# Filters_3Stage_Circuit_Manual.net
KiCad netlist of a schematic drawn in EAGLE
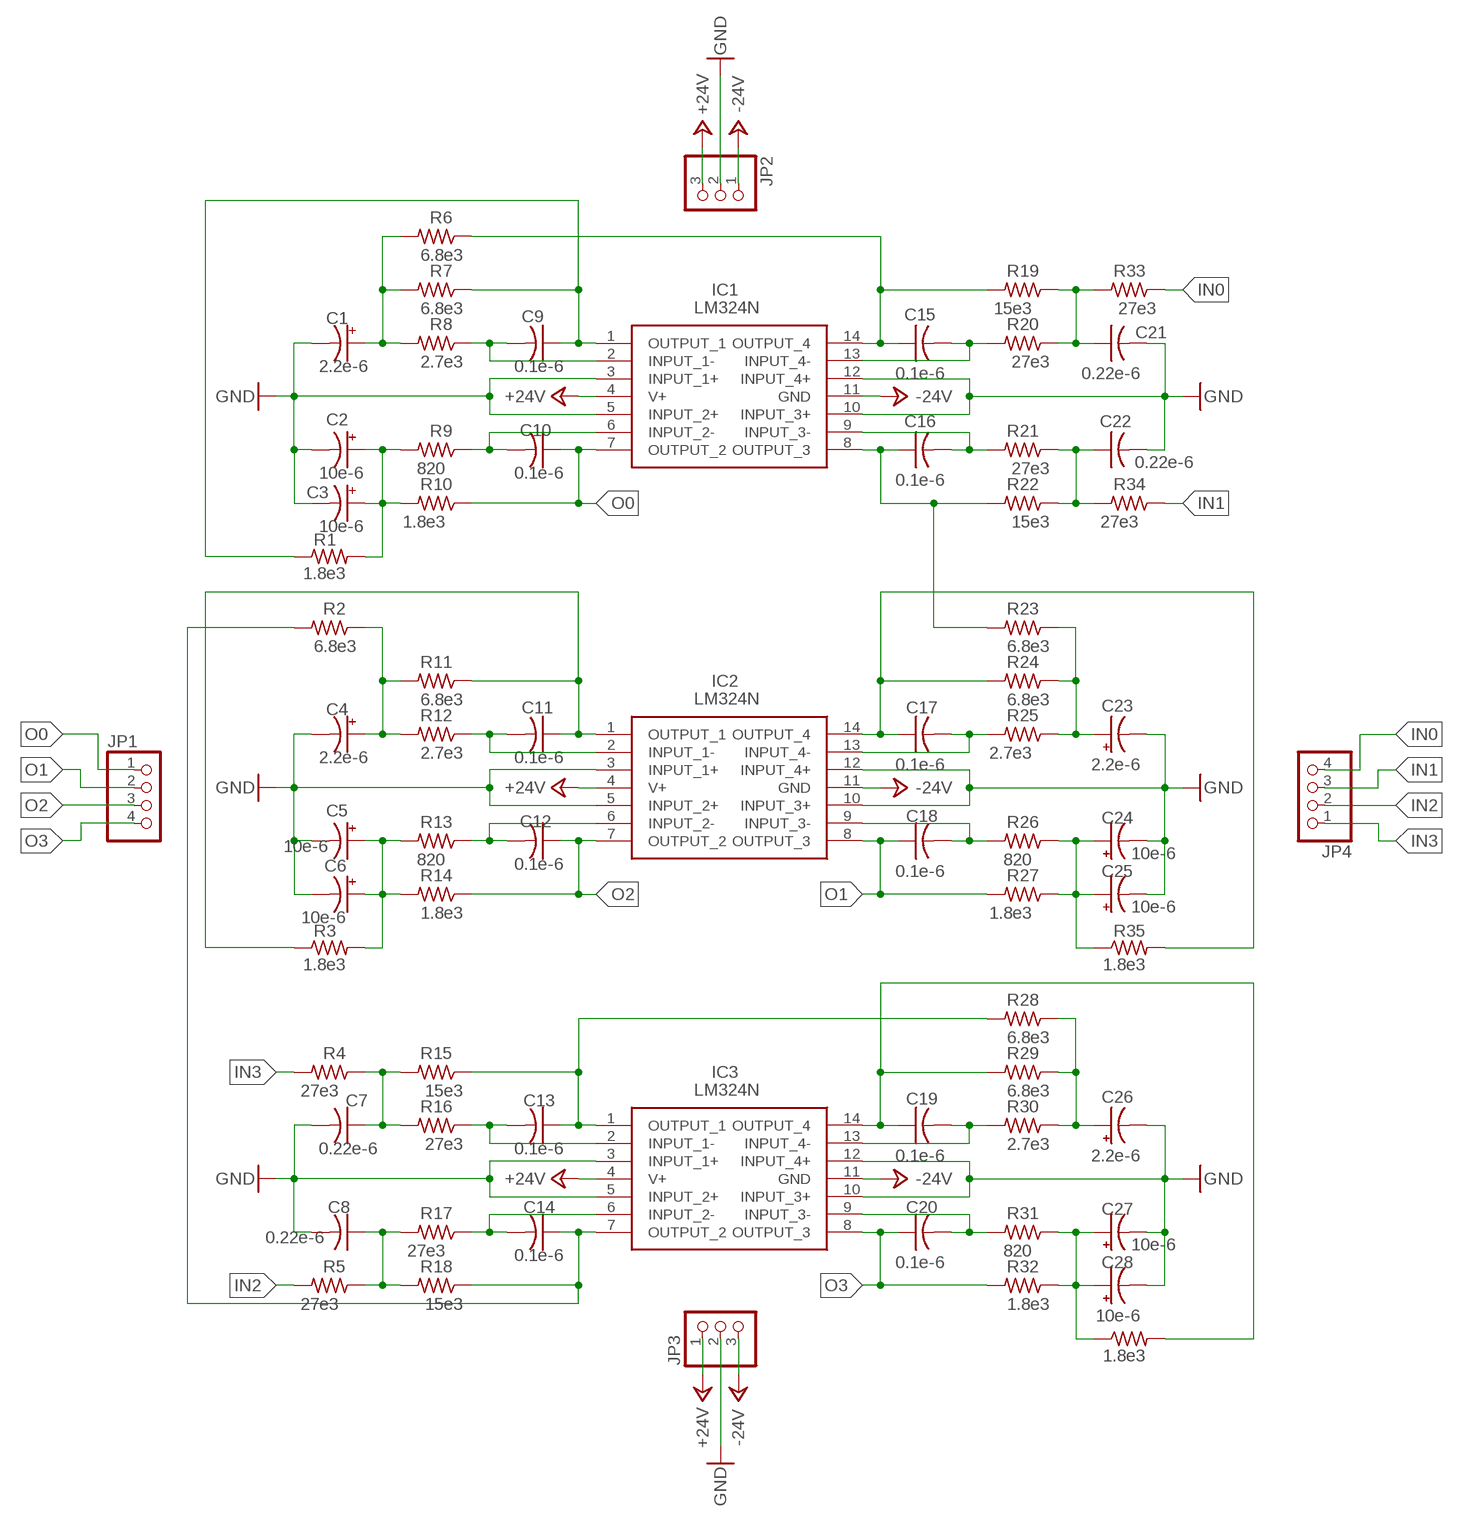
[diagram p0: schematic, sheet 1]

(export (version "E")
  (design (tool "Eeschema 10.0.6"))
  (components
    (comp (ref "C1")
      (value "2.2e-6")
      (footprint "eagle-import:E2,5-5")
      (libsource (lib "eagle-import") (part "CPOL-USE2.5-5"))
    )
    (comp (ref "C2")
      (value "10e-6")
      (footprint "eagle-import:E2,5-7")
      (libsource (lib "eagle-import") (part "CPOL-USE2.5-7"))
    )
    (comp (ref "C3")
      (value "10e-6")
      (footprint "eagle-import:E2,5-7")
      (libsource (lib "eagle-import") (part "CPOL-USE2.5-7"))
    )
    (comp (ref "C4")
      (value "2.2e-6")
      (footprint "eagle-import:E2,5-5")
      (libsource (lib "eagle-import") (part "CPOL-USE2.5-5"))
    )
    (comp (ref "C5")
      (value "10e-6")
      (footprint "eagle-import:E2,5-7")
      (libsource (lib "eagle-import") (part "CPOL-USE2.5-7"))
    )
    (comp (ref "C6")
      (value "10e-6")
      (footprint "eagle-import:E2,5-7")
      (libsource (lib "eagle-import") (part "CPOL-USE2.5-7"))
    )
    (comp (ref "C7")
      (value "0.22e-6")
      (footprint "eagle-import:C050-030X075")
      (libsource (lib "eagle-import") (part "C-US050-030X075"))
    )
    (comp (ref "C8")
      (value "0.22e-6")
      (footprint "eagle-import:C050-030X075")
      (libsource (lib "eagle-import") (part "C-US050-030X075"))
    )
    (comp (ref "C9")
      (value "0.1e-6")
      (footprint "eagle-import:C050-030X075")
      (libsource (lib "eagle-import") (part "C-US050-030X075"))
    )
    (comp (ref "C10")
      (value "0.1e-6")
      (footprint "eagle-import:C050-030X075")
      (libsource (lib "eagle-import") (part "C-US050-030X075"))
    )
    (comp (ref "C11")
      (value "0.1e-6")
      (footprint "eagle-import:C050-030X075")
      (libsource (lib "eagle-import") (part "C-US050-030X075"))
    )
    (comp (ref "C12")
      (value "0.1e-6")
      (footprint "eagle-import:C050-030X075")
      (libsource (lib "eagle-import") (part "C-US050-030X075"))
    )
    (comp (ref "C13")
      (value "0.1e-6")
      (footprint "eagle-import:C050-030X075")
      (libsource (lib "eagle-import") (part "C-US050-030X075"))
    )
    (comp (ref "C14")
      (value "0.1e-6")
      (footprint "eagle-import:C050-030X075")
      (libsource (lib "eagle-import") (part "C-US050-030X075"))
    )
    (comp (ref "C15")
      (value "0.1e-6")
      (footprint "eagle-import:C050-030X075")
      (libsource (lib "eagle-import") (part "C-US050-030X075"))
    )
    (comp (ref "C16")
      (value "0.1e-6")
      (footprint "eagle-import:C050-030X075")
      (libsource (lib "eagle-import") (part "C-US050-030X075"))
    )
    (comp (ref "C17")
      (value "0.1e-6")
      (footprint "eagle-import:C050-030X075")
      (libsource (lib "eagle-import") (part "C-US050-030X075"))
    )
    (comp (ref "C18")
      (value "0.1e-6")
      (footprint "eagle-import:C050-030X075")
      (libsource (lib "eagle-import") (part "C-US050-030X075"))
    )
    (comp (ref "C19")
      (value "0.1e-6")
      (footprint "eagle-import:C050-030X075")
      (libsource (lib "eagle-import") (part "C-US050-030X075"))
    )
    (comp (ref "C20")
      (value "0.1e-6")
      (footprint "eagle-import:C050-030X075")
      (libsource (lib "eagle-import") (part "C-US050-030X075"))
    )
    (comp (ref "C21")
      (value "0.22e-6")
      (footprint "eagle-import:C050-030X075")
      (libsource (lib "eagle-import") (part "C-US050-030X075"))
    )
    (comp (ref "C22")
      (value "0.22e-6")
      (footprint "eagle-import:C050-030X075")
      (libsource (lib "eagle-import") (part "C-US050-030X075"))
    )
    (comp (ref "C23")
      (value "2.2e-6")
      (footprint "eagle-import:E2,5-5")
      (libsource (lib "eagle-import") (part "CPOL-USE2.5-5"))
    )
    (comp (ref "C24")
      (value "10e-6")
      (footprint "eagle-import:E2,5-7")
      (libsource (lib "eagle-import") (part "CPOL-USE2.5-7"))
    )
    (comp (ref "C25")
      (value "10e-6")
      (footprint "eagle-import:E2,5-7")
      (libsource (lib "eagle-import") (part "CPOL-USE2.5-7"))
    )
    (comp (ref "C26")
      (value "2.2e-6")
      (footprint "eagle-import:E2,5-5")
      (libsource (lib "eagle-import") (part "CPOL-USE2.5-5"))
    )
    (comp (ref "C27")
      (value "10e-6")
      (footprint "eagle-import:E2,5-7")
      (libsource (lib "eagle-import") (part "CPOL-USE2.5-7"))
    )
    (comp (ref "C28")
      (value "10e-6")
      (footprint "eagle-import:E2,5-7")
      (libsource (lib "eagle-import") (part "CPOL-USE2.5-7"))
    )
    (comp (ref "IC1")
      (value "LM324N")
      (footprint "eagle-import:DIP794W56P254L1905H533Q14N")
      (fields (field (name "MOUSER_PART_NUMBER") "595-LM324N"))
      (libsource (lib "eagle-import") (part "LM324N"))
    )
    (comp (ref "IC2")
      (value "LM324N")
      (footprint "eagle-import:DIP794W56P254L1905H533Q14N")
      (fields (field (name "MOUSER_PART_NUMBER") "595-LM324N"))
      (libsource (lib "eagle-import") (part "LM324N"))
    )
    (comp (ref "IC3")
      (value "LM324N")
      (footprint "eagle-import:DIP794W56P254L1905H533Q14N")
      (fields (field (name "MOUSER_PART_NUMBER") "595-LM324N"))
      (libsource (lib "eagle-import") (part "LM324N"))
    )
    (comp (ref "JP1")
      (value "PINHD-1X4")
      (footprint "eagle-import:1X04")
      (libsource (lib "eagle-import") (part "PINHD-1X4"))
    )
    (comp (ref "JP2")
      (value "PINHD-1X3")
      (footprint "eagle-import:1X03")
      (libsource (lib "eagle-import") (part "PINHD-1X3"))
    )
    (comp (ref "JP3")
      (value "PINHD-1X3")
      (footprint "eagle-import:1X03")
      (libsource (lib "eagle-import") (part "PINHD-1X3"))
    )
    (comp (ref "JP4")
      (value "PINHD-1X4")
      (footprint "eagle-import:1X04")
      (libsource (lib "eagle-import") (part "PINHD-1X4"))
    )
    (comp (ref "R1")
      (value "1.8e3")
      (footprint "eagle-import:0207_10")
      (libsource (lib "eagle-import") (part "R-US_0207/10"))
    )
    (comp (ref "R2")
      (value "6.8e3")
      (footprint "eagle-import:0207_10")
      (libsource (lib "eagle-import") (part "R-US_0207/10"))
    )
    (comp (ref "R3")
      (value "1.8e3")
      (footprint "eagle-import:0207_10")
      (libsource (lib "eagle-import") (part "R-US_0207/10"))
    )
    (comp (ref "R4")
      (value "27e3")
      (footprint "eagle-import:0207_10")
      (libsource (lib "eagle-import") (part "R-US_0207/10"))
    )
    (comp (ref "R5")
      (value "27e3")
      (footprint "eagle-import:0207_10")
      (libsource (lib "eagle-import") (part "R-US_0207/10"))
    )
    (comp (ref "R6")
      (value "6.8e3")
      (footprint "eagle-import:0207_10")
      (libsource (lib "eagle-import") (part "R-US_0207/10"))
    )
    (comp (ref "R7")
      (value "6.8e3")
      (footprint "eagle-import:0207_10")
      (libsource (lib "eagle-import") (part "R-US_0207/10"))
    )
    (comp (ref "R8")
      (value "2.7e3")
      (footprint "eagle-import:0207_10")
      (libsource (lib "eagle-import") (part "R-US_0207/10"))
    )
    (comp (ref "R9")
      (value "820")
      (footprint "eagle-import:0207_10")
      (libsource (lib "eagle-import") (part "R-US_0207/10"))
    )
    (comp (ref "R10")
      (value "1.8e3")
      (footprint "eagle-import:0207_10")
      (libsource (lib "eagle-import") (part "R-US_0207/10"))
    )
    (comp (ref "R11")
      (value "6.8e3")
      (footprint "eagle-import:0207_10")
      (libsource (lib "eagle-import") (part "R-US_0207/10"))
    )
    (comp (ref "R12")
      (value "2.7e3")
      (footprint "eagle-import:0207_10")
      (libsource (lib "eagle-import") (part "R-US_0207/10"))
    )
    (comp (ref "R13")
      (value "820")
      (footprint "eagle-import:0207_10")
      (libsource (lib "eagle-import") (part "R-US_0207/10"))
    )
    (comp (ref "R14")
      (value "1.8e3")
      (footprint "eagle-import:0207_10")
      (libsource (lib "eagle-import") (part "R-US_0207/10"))
    )
    (comp (ref "R15")
      (value "15e3")
      (footprint "eagle-import:0207_10")
      (libsource (lib "eagle-import") (part "R-US_0207/10"))
    )
    (comp (ref "R16")
      (value "27e3")
      (footprint "eagle-import:0207_10")
      (libsource (lib "eagle-import") (part "R-US_0207/10"))
    )
    (comp (ref "R17")
      (value "27e3")
      (footprint "eagle-import:0207_10")
      (libsource (lib "eagle-import") (part "R-US_0207/10"))
    )
    (comp (ref "R18")
      (value "15e3")
      (footprint "eagle-import:0207_10")
      (libsource (lib "eagle-import") (part "R-US_0207/10"))
    )
    (comp (ref "R19")
      (value "15e3")
      (footprint "eagle-import:0207_10")
      (libsource (lib "eagle-import") (part "R-US_0207/10"))
    )
    (comp (ref "R20")
      (value "27e3")
      (footprint "eagle-import:0207_10")
      (libsource (lib "eagle-import") (part "R-US_0207/10"))
    )
    (comp (ref "R21")
      (value "27e3")
      (footprint "eagle-import:0207_10")
      (libsource (lib "eagle-import") (part "R-US_0207/10"))
    )
    (comp (ref "R22")
      (value "15e3")
      (footprint "eagle-import:0207_10")
      (libsource (lib "eagle-import") (part "R-US_0207/10"))
    )
    (comp (ref "R23")
      (value "6.8e3")
      (footprint "eagle-import:0207_10")
      (libsource (lib "eagle-import") (part "R-US_0207/10"))
    )
    (comp (ref "R24")
      (value "6.8e3")
      (footprint "eagle-import:0207_10")
      (libsource (lib "eagle-import") (part "R-US_0207/10"))
    )
    (comp (ref "R25")
      (value "2.7e3")
      (footprint "eagle-import:0207_10")
      (libsource (lib "eagle-import") (part "R-US_0207/10"))
    )
    (comp (ref "R26")
      (value "820")
      (footprint "eagle-import:0207_10")
      (libsource (lib "eagle-import") (part "R-US_0207/10"))
    )
    (comp (ref "R27")
      (value "1.8e3")
      (footprint "eagle-import:0207_10")
      (libsource (lib "eagle-import") (part "R-US_0207/10"))
    )
    (comp (ref "R28")
      (value "6.8e3")
      (footprint "eagle-import:0207_10")
      (libsource (lib "eagle-import") (part "R-US_0207/10"))
    )
    (comp (ref "R29")
      (value "6.8e3")
      (footprint "eagle-import:0207_10")
      (libsource (lib "eagle-import") (part "R-US_0207/10"))
    )
    (comp (ref "R30")
      (value "2.7e3")
      (footprint "eagle-import:0207_10")
      (libsource (lib "eagle-import") (part "R-US_0207/10"))
    )
    (comp (ref "R31")
      (value "820")
      (footprint "eagle-import:0207_10")
      (libsource (lib "eagle-import") (part "R-US_0207/10"))
    )
    (comp (ref "R32")
      (value "1.8e3")
      (footprint "eagle-import:0207_10")
      (libsource (lib "eagle-import") (part "R-US_0207/10"))
    )
    (comp (ref "R33")
      (value "27e3")
      (footprint "eagle-import:0207_10")
      (libsource (lib "eagle-import") (part "R-US_0207/10"))
    )
    (comp (ref "R34")
      (value "27e3")
      (footprint "eagle-import:0207_10")
      (libsource (lib "eagle-import") (part "R-US_0207/10"))
    )
    (comp (ref "R35")
      (value "1.8e3")
      (footprint "eagle-import:0207_10")
      (libsource (lib "eagle-import") (part "R-US_0207/10"))
    )
    (comp (ref "R36")
      (value "1.8e3")
      (footprint "eagle-import:0207_10")
      (libsource (lib "eagle-import") (part "R-US_0207/10"))
    )
  )
  (nets
    (net (code "1") (name "+24V") (class "Default")
      (node (ref "IC1") (pin "4") (pinfunction "V+_4") (pintype "bidirectional"))
      (node (ref "IC2") (pin "4") (pinfunction "V+_4") (pintype "bidirectional"))
      (node (ref "IC3") (pin "4") (pinfunction "V+_4") (pintype "bidirectional"))
      (node (ref "JP2") (pin "3") (pinfunction "3_3") (pintype "passive"))
      (node (ref "JP3") (pin "1") (pinfunction "1_1") (pintype "passive"))
    )
    (net (code "2") (name "-24V") (class "Default")
      (node (ref "IC1") (pin "11") (pinfunction "GND_11") (pintype "bidirectional"))
      (node (ref "IC2") (pin "11") (pinfunction "GND_11") (pintype "bidirectional"))
      (node (ref "IC3") (pin "11") (pinfunction "GND_11") (pintype "bidirectional"))
      (node (ref "JP2") (pin "1") (pinfunction "1_1") (pintype "passive"))
      (node (ref "JP3") (pin "3") (pinfunction "3_3") (pintype "passive"))
    )
    (net (code "3") (name "GND") (class "Default")
      (node (ref "C1") (pin "-") (pinfunction "-_-") (pintype "passive"))
      (node (ref "C2") (pin "-") (pinfunction "-_-") (pintype "passive"))
      (node (ref "C21") (pin "2") (pinfunction "2_2") (pintype "passive"))
      (node (ref "C22") (pin "2") (pinfunction "2_2") (pintype "passive"))
      (node (ref "C23") (pin "-") (pinfunction "-_-") (pintype "passive"))
      (node (ref "C24") (pin "-") (pinfunction "-_-") (pintype "passive"))
      (node (ref "C25") (pin "-") (pinfunction "-_-") (pintype "passive"))
      (node (ref "C26") (pin "-") (pinfunction "-_-") (pintype "passive"))
      (node (ref "C27") (pin "-") (pinfunction "-_-") (pintype "passive"))
      (node (ref "C28") (pin "-") (pinfunction "-_-") (pintype "passive"))
      (node (ref "C3") (pin "-") (pinfunction "-_-") (pintype "passive"))
      (node (ref "C4") (pin "-") (pinfunction "-_-") (pintype "passive"))
      (node (ref "C5") (pin "-") (pinfunction "-_-") (pintype "passive"))
      (node (ref "C6") (pin "-") (pinfunction "-_-") (pintype "passive"))
      (node (ref "C7") (pin "2") (pinfunction "2_2") (pintype "passive"))
      (node (ref "C8") (pin "2") (pinfunction "2_2") (pintype "passive"))
      (node (ref "IC1") (pin "10") (pinfunction "INPUT_3+_10") (pintype "bidirectional"))
      (node (ref "IC1") (pin "12") (pinfunction "INPUT_4+_12") (pintype "bidirectional"))
      (node (ref "IC1") (pin "3") (pinfunction "INPUT_1+_3") (pintype "bidirectional"))
      (node (ref "IC1") (pin "5") (pinfunction "INPUT_2+_5") (pintype "bidirectional"))
      (node (ref "IC2") (pin "10") (pinfunction "INPUT_3+_10") (pintype "bidirectional"))
      (node (ref "IC2") (pin "12") (pinfunction "INPUT_4+_12") (pintype "bidirectional"))
      (node (ref "IC2") (pin "3") (pinfunction "INPUT_1+_3") (pintype "bidirectional"))
      (node (ref "IC2") (pin "5") (pinfunction "INPUT_2+_5") (pintype "bidirectional"))
      (node (ref "IC3") (pin "10") (pinfunction "INPUT_3+_10") (pintype "bidirectional"))
      (node (ref "IC3") (pin "12") (pinfunction "INPUT_4+_12") (pintype "bidirectional"))
      (node (ref "IC3") (pin "3") (pinfunction "INPUT_1+_3") (pintype "bidirectional"))
      (node (ref "IC3") (pin "5") (pinfunction "INPUT_2+_5") (pintype "bidirectional"))
      (node (ref "JP2") (pin "2") (pinfunction "2_2") (pintype "passive"))
      (node (ref "JP3") (pin "2") (pinfunction "2_2") (pintype "passive"))
    )
    (net (code "4") (name "IN0") (class "Default")
      (node (ref "JP4") (pin "4") (pinfunction "4_4") (pintype "passive"))
      (node (ref "R33") (pin "1") (pinfunction "1_1") (pintype "passive"))
    )
    (net (code "5") (name "IN1") (class "Default")
      (node (ref "JP4") (pin "3") (pinfunction "3_3") (pintype "passive"))
      (node (ref "R34") (pin "1") (pinfunction "1_1") (pintype "passive"))
    )
    (net (code "6") (name "IN2") (class "Default")
      (node (ref "JP4") (pin "2") (pinfunction "2_2") (pintype "passive"))
      (node (ref "R5") (pin "2") (pinfunction "2_2") (pintype "passive"))
    )
    (net (code "7") (name "IN3") (class "Default")
      (node (ref "JP4") (pin "1") (pinfunction "1_1") (pintype "passive"))
      (node (ref "R4") (pin "2") (pinfunction "2_2") (pintype "passive"))
    )
    (net (code "8") (name "Net-(C1-Pad+)") (class "Default")
      (node (ref "C1") (pin "+") (pinfunction "+_+") (pintype "passive"))
      (node (ref "R6") (pin "2") (pinfunction "2_2") (pintype "passive"))
      (node (ref "R7") (pin "2") (pinfunction "2_2") (pintype "passive"))
      (node (ref "R8") (pin "2") (pinfunction "2_2") (pintype "passive"))
    )
    (net (code "9") (name "Net-(C2-Pad+)") (class "Default")
      (node (ref "C2") (pin "+") (pinfunction "+_+") (pintype "passive"))
      (node (ref "C3") (pin "+") (pinfunction "+_+") (pintype "passive"))
      (node (ref "R1") (pin "2") (pinfunction "2_2") (pintype "passive"))
      (node (ref "R10") (pin "2") (pinfunction "2_2") (pintype "passive"))
      (node (ref "R9") (pin "2") (pinfunction "2_2") (pintype "passive"))
    )
    (net (code "10") (name "Net-(C4-Pad+)") (class "Default")
      (node (ref "C4") (pin "+") (pinfunction "+_+") (pintype "passive"))
      (node (ref "R11") (pin "2") (pinfunction "2_2") (pintype "passive"))
      (node (ref "R12") (pin "2") (pinfunction "2_2") (pintype "passive"))
      (node (ref "R2") (pin "1") (pinfunction "1_1") (pintype "passive"))
    )
    (net (code "11") (name "Net-(C5-Pad+)") (class "Default")
      (node (ref "C5") (pin "+") (pinfunction "+_+") (pintype "passive"))
      (node (ref "C6") (pin "+") (pinfunction "+_+") (pintype "passive"))
      (node (ref "R13") (pin "2") (pinfunction "2_2") (pintype "passive"))
      (node (ref "R14") (pin "2") (pinfunction "2_2") (pintype "passive"))
      (node (ref "R3") (pin "2") (pinfunction "2_2") (pintype "passive"))
    )
    (net (code "12") (name "Net-(C7-Pad1)") (class "Default")
      (node (ref "C7") (pin "1") (pinfunction "1_1") (pintype "passive"))
      (node (ref "R15") (pin "2") (pinfunction "2_2") (pintype "passive"))
      (node (ref "R16") (pin "2") (pinfunction "2_2") (pintype "passive"))
      (node (ref "R4") (pin "1") (pinfunction "1_1") (pintype "passive"))
    )
    (net (code "13") (name "Net-(C8-Pad1)") (class "Default")
      (node (ref "C8") (pin "1") (pinfunction "1_1") (pintype "passive"))
      (node (ref "R17") (pin "2") (pinfunction "2_2") (pintype "passive"))
      (node (ref "R18") (pin "2") (pinfunction "2_2") (pintype "passive"))
      (node (ref "R5") (pin "1") (pinfunction "1_1") (pintype "passive"))
    )
    (net (code "14") (name "Net-(C21-Pad1)") (class "Default")
      (node (ref "C21") (pin "1") (pinfunction "1_1") (pintype "passive"))
      (node (ref "R19") (pin "1") (pinfunction "1_1") (pintype "passive"))
      (node (ref "R20") (pin "1") (pinfunction "1_1") (pintype "passive"))
      (node (ref "R33") (pin "2") (pinfunction "2_2") (pintype "passive"))
    )
    (net (code "15") (name "Net-(C22-Pad1)") (class "Default")
      (node (ref "C22") (pin "1") (pinfunction "1_1") (pintype "passive"))
      (node (ref "R21") (pin "1") (pinfunction "1_1") (pintype "passive"))
      (node (ref "R22") (pin "1") (pinfunction "1_1") (pintype "passive"))
      (node (ref "R34") (pin "2") (pinfunction "2_2") (pintype "passive"))
    )
    (net (code "16") (name "Net-(C23-Pad+)") (class "Default")
      (node (ref "C23") (pin "+") (pinfunction "+_+") (pintype "passive"))
      (node (ref "R23") (pin "1") (pinfunction "1_1") (pintype "passive"))
      (node (ref "R24") (pin "1") (pinfunction "1_1") (pintype "passive"))
      (node (ref "R25") (pin "1") (pinfunction "1_1") (pintype "passive"))
    )
    (net (code "17") (name "Net-(C24-Pad+)") (class "Default")
      (node (ref "C24") (pin "+") (pinfunction "+_+") (pintype "passive"))
      (node (ref "C25") (pin "+") (pinfunction "+_+") (pintype "passive"))
      (node (ref "R26") (pin "1") (pinfunction "1_1") (pintype "passive"))
      (node (ref "R27") (pin "1") (pinfunction "1_1") (pintype "passive"))
      (node (ref "R35") (pin "1") (pinfunction "1_1") (pintype "passive"))
    )
    (net (code "18") (name "Net-(C26-Pad+)") (class "Default")
      (node (ref "C26") (pin "+") (pinfunction "+_+") (pintype "passive"))
      (node (ref "R28") (pin "1") (pinfunction "1_1") (pintype "passive"))
      (node (ref "R29") (pin "1") (pinfunction "1_1") (pintype "passive"))
      (node (ref "R30") (pin "1") (pinfunction "1_1") (pintype "passive"))
    )
    (net (code "19") (name "Net-(C27-Pad+)") (class "Default")
      (node (ref "C27") (pin "+") (pinfunction "+_+") (pintype "passive"))
      (node (ref "C28") (pin "+") (pinfunction "+_+") (pintype "passive"))
      (node (ref "R31") (pin "1") (pinfunction "1_1") (pintype "passive"))
      (node (ref "R32") (pin "1") (pinfunction "1_1") (pintype "passive"))
      (node (ref "R36") (pin "1") (pinfunction "1_1") (pintype "passive"))
    )
    (net (code "20") (name "Net-(IC1-INPUT_1-)") (class "Default")
      (node (ref "C9") (pin "2") (pinfunction "2_2") (pintype "passive"))
      (node (ref "IC1") (pin "2") (pinfunction "INPUT_1-_2") (pintype "bidirectional"))
      (node (ref "R8") (pin "1") (pinfunction "1_1") (pintype "passive"))
    )
    (net (code "21") (name "Net-(IC1-INPUT_2-)") (class "Default")
      (node (ref "C10") (pin "2") (pinfunction "2_2") (pintype "passive"))
      (node (ref "IC1") (pin "6") (pinfunction "INPUT_2-_6") (pintype "bidirectional"))
      (node (ref "R9") (pin "1") (pinfunction "1_1") (pintype "passive"))
    )
    (net (code "22") (name "Net-(IC1-INPUT_3-)") (class "Default")
      (node (ref "C16") (pin "2") (pinfunction "2_2") (pintype "passive"))
      (node (ref "IC1") (pin "9") (pinfunction "INPUT_3-_9") (pintype "bidirectional"))
      (node (ref "R21") (pin "2") (pinfunction "2_2") (pintype "passive"))
    )
    (net (code "23") (name "Net-(IC1-INPUT_4-)") (class "Default")
      (node (ref "C15") (pin "2") (pinfunction "2_2") (pintype "passive"))
      (node (ref "IC1") (pin "13") (pinfunction "INPUT_4-_13") (pintype "bidirectional"))
      (node (ref "R20") (pin "2") (pinfunction "2_2") (pintype "passive"))
    )
    (net (code "24") (name "Net-(IC1-OUTPUT_1)") (class "Default")
      (node (ref "C9") (pin "1") (pinfunction "1_1") (pintype "passive"))
      (node (ref "IC1") (pin "1") (pinfunction "OUTPUT_1_1") (pintype "bidirectional"))
      (node (ref "R1") (pin "1") (pinfunction "1_1") (pintype "passive"))
      (node (ref "R7") (pin "1") (pinfunction "1_1") (pintype "passive"))
    )
    (net (code "25") (name "Net-(IC1-OUTPUT_3)") (class "Default")
      (node (ref "C16") (pin "1") (pinfunction "1_1") (pintype "passive"))
      (node (ref "IC1") (pin "8") (pinfunction "OUTPUT_3_8") (pintype "bidirectional"))
      (node (ref "R22") (pin "2") (pinfunction "2_2") (pintype "passive"))
      (node (ref "R23") (pin "2") (pinfunction "2_2") (pintype "passive"))
    )
    (net (code "26") (name "Net-(IC1-OUTPUT_4)") (class "Default")
      (node (ref "C15") (pin "1") (pinfunction "1_1") (pintype "passive"))
      (node (ref "IC1") (pin "14") (pinfunction "OUTPUT_4_14") (pintype "bidirectional"))
      (node (ref "R19") (pin "2") (pinfunction "2_2") (pintype "passive"))
      (node (ref "R6") (pin "1") (pinfunction "1_1") (pintype "passive"))
    )
    (net (code "27") (name "Net-(IC2-INPUT_1-)") (class "Default")
      (node (ref "C11") (pin "2") (pinfunction "2_2") (pintype "passive"))
      (node (ref "IC2") (pin "2") (pinfunction "INPUT_1-_2") (pintype "bidirectional"))
      (node (ref "R12") (pin "1") (pinfunction "1_1") (pintype "passive"))
    )
    (net (code "28") (name "Net-(IC2-INPUT_2-)") (class "Default")
      (node (ref "C12") (pin "2") (pinfunction "2_2") (pintype "passive"))
      (node (ref "IC2") (pin "6") (pinfunction "INPUT_2-_6") (pintype "bidirectional"))
      (node (ref "R13") (pin "1") (pinfunction "1_1") (pintype "passive"))
    )
    (net (code "29") (name "Net-(IC2-INPUT_3-)") (class "Default")
      (node (ref "C18") (pin "2") (pinfunction "2_2") (pintype "passive"))
      (node (ref "IC2") (pin "9") (pinfunction "INPUT_3-_9") (pintype "bidirectional"))
      (node (ref "R26") (pin "2") (pinfunction "2_2") (pintype "passive"))
    )
    (net (code "30") (name "Net-(IC2-INPUT_4-)") (class "Default")
      (node (ref "C17") (pin "2") (pinfunction "2_2") (pintype "passive"))
      (node (ref "IC2") (pin "13") (pinfunction "INPUT_4-_13") (pintype "bidirectional"))
      (node (ref "R25") (pin "2") (pinfunction "2_2") (pintype "passive"))
    )
    (net (code "31") (name "Net-(IC2-OUTPUT_1)") (class "Default")
      (node (ref "C11") (pin "1") (pinfunction "1_1") (pintype "passive"))
      (node (ref "IC2") (pin "1") (pinfunction "OUTPUT_1_1") (pintype "bidirectional"))
      (node (ref "R11") (pin "1") (pinfunction "1_1") (pintype "passive"))
      (node (ref "R3") (pin "1") (pinfunction "1_1") (pintype "passive"))
    )
    (net (code "32") (name "Net-(IC2-OUTPUT_4)") (class "Default")
      (node (ref "C17") (pin "1") (pinfunction "1_1") (pintype "passive"))
      (node (ref "IC2") (pin "14") (pinfunction "OUTPUT_4_14") (pintype "bidirectional"))
      (node (ref "R24") (pin "2") (pinfunction "2_2") (pintype "passive"))
      (node (ref "R35") (pin "2") (pinfunction "2_2") (pintype "passive"))
    )
    (net (code "33") (name "Net-(IC3-INPUT_1-)") (class "Default")
      (node (ref "C13") (pin "2") (pinfunction "2_2") (pintype "passive"))
      (node (ref "IC3") (pin "2") (pinfunction "INPUT_1-_2") (pintype "bidirectional"))
      (node (ref "R16") (pin "1") (pinfunction "1_1") (pintype "passive"))
    )
    (net (code "34") (name "Net-(IC3-INPUT_2-)") (class "Default")
      (node (ref "C14") (pin "2") (pinfunction "2_2") (pintype "passive"))
      (node (ref "IC3") (pin "6") (pinfunction "INPUT_2-_6") (pintype "bidirectional"))
      (node (ref "R17") (pin "1") (pinfunction "1_1") (pintype "passive"))
    )
    (net (code "35") (name "Net-(IC3-INPUT_3-)") (class "Default")
      (node (ref "C20") (pin "2") (pinfunction "2_2") (pintype "passive"))
      (node (ref "IC3") (pin "9") (pinfunction "INPUT_3-_9") (pintype "bidirectional"))
      (node (ref "R31") (pin "2") (pinfunction "2_2") (pintype "passive"))
    )
    (net (code "36") (name "Net-(IC3-INPUT_4-)") (class "Default")
      (node (ref "C19") (pin "2") (pinfunction "2_2") (pintype "passive"))
      (node (ref "IC3") (pin "13") (pinfunction "INPUT_4-_13") (pintype "bidirectional"))
      (node (ref "R30") (pin "2") (pinfunction "2_2") (pintype "passive"))
    )
    (net (code "37") (name "Net-(IC3-OUTPUT_1)") (class "Default")
      (node (ref "C13") (pin "1") (pinfunction "1_1") (pintype "passive"))
      (node (ref "IC3") (pin "1") (pinfunction "OUTPUT_1_1") (pintype "bidirectional"))
      (node (ref "R15") (pin "1") (pinfunction "1_1") (pintype "passive"))
      (node (ref "R28") (pin "2") (pinfunction "2_2") (pintype "passive"))
    )
    (net (code "38") (name "Net-(IC3-OUTPUT_2)") (class "Default")
      (node (ref "C14") (pin "1") (pinfunction "1_1") (pintype "passive"))
      (node (ref "IC3") (pin "7") (pinfunction "OUTPUT_2_7") (pintype "bidirectional"))
      (node (ref "R18") (pin "1") (pinfunction "1_1") (pintype "passive"))
      (node (ref "R2") (pin "2") (pinfunction "2_2") (pintype "passive"))
    )
    (net (code "39") (name "Net-(IC3-OUTPUT_4)") (class "Default")
      (node (ref "C19") (pin "1") (pinfunction "1_1") (pintype "passive"))
      (node (ref "IC3") (pin "14") (pinfunction "OUTPUT_4_14") (pintype "bidirectional"))
      (node (ref "R29") (pin "2") (pinfunction "2_2") (pintype "passive"))
      (node (ref "R36") (pin "2") (pinfunction "2_2") (pintype "passive"))
    )
    (net (code "40") (name "O0") (class "Default")
      (node (ref "C10") (pin "1") (pinfunction "1_1") (pintype "passive"))
      (node (ref "IC1") (pin "7") (pinfunction "OUTPUT_2_7") (pintype "bidirectional"))
      (node (ref "JP1") (pin "1") (pinfunction "1_1") (pintype "passive"))
      (node (ref "R10") (pin "1") (pinfunction "1_1") (pintype "passive"))
    )
    (net (code "41") (name "O1") (class "Default")
      (node (ref "C18") (pin "1") (pinfunction "1_1") (pintype "passive"))
      (node (ref "IC2") (pin "8") (pinfunction "OUTPUT_3_8") (pintype "bidirectional"))
      (node (ref "JP1") (pin "2") (pinfunction "2_2") (pintype "passive"))
      (node (ref "R27") (pin "2") (pinfunction "2_2") (pintype "passive"))
    )
    (net (code "42") (name "O2") (class "Default")
      (node (ref "C12") (pin "1") (pinfunction "1_1") (pintype "passive"))
      (node (ref "IC2") (pin "7") (pinfunction "OUTPUT_2_7") (pintype "bidirectional"))
      (node (ref "JP1") (pin "3") (pinfunction "3_3") (pintype "passive"))
      (node (ref "R14") (pin "1") (pinfunction "1_1") (pintype "passive"))
    )
    (net (code "43") (name "O3") (class "Default")
      (node (ref "C20") (pin "1") (pinfunction "1_1") (pintype "passive"))
      (node (ref "IC3") (pin "8") (pinfunction "OUTPUT_3_8") (pintype "bidirectional"))
      (node (ref "JP1") (pin "4") (pinfunction "4_4") (pintype "passive"))
      (node (ref "R32") (pin "2") (pinfunction "2_2") (pintype "passive"))
    )
  )
)
